# pcb_rfic_nrf905_final.net
KiCad netlist of a schematic drawn in EAGLE
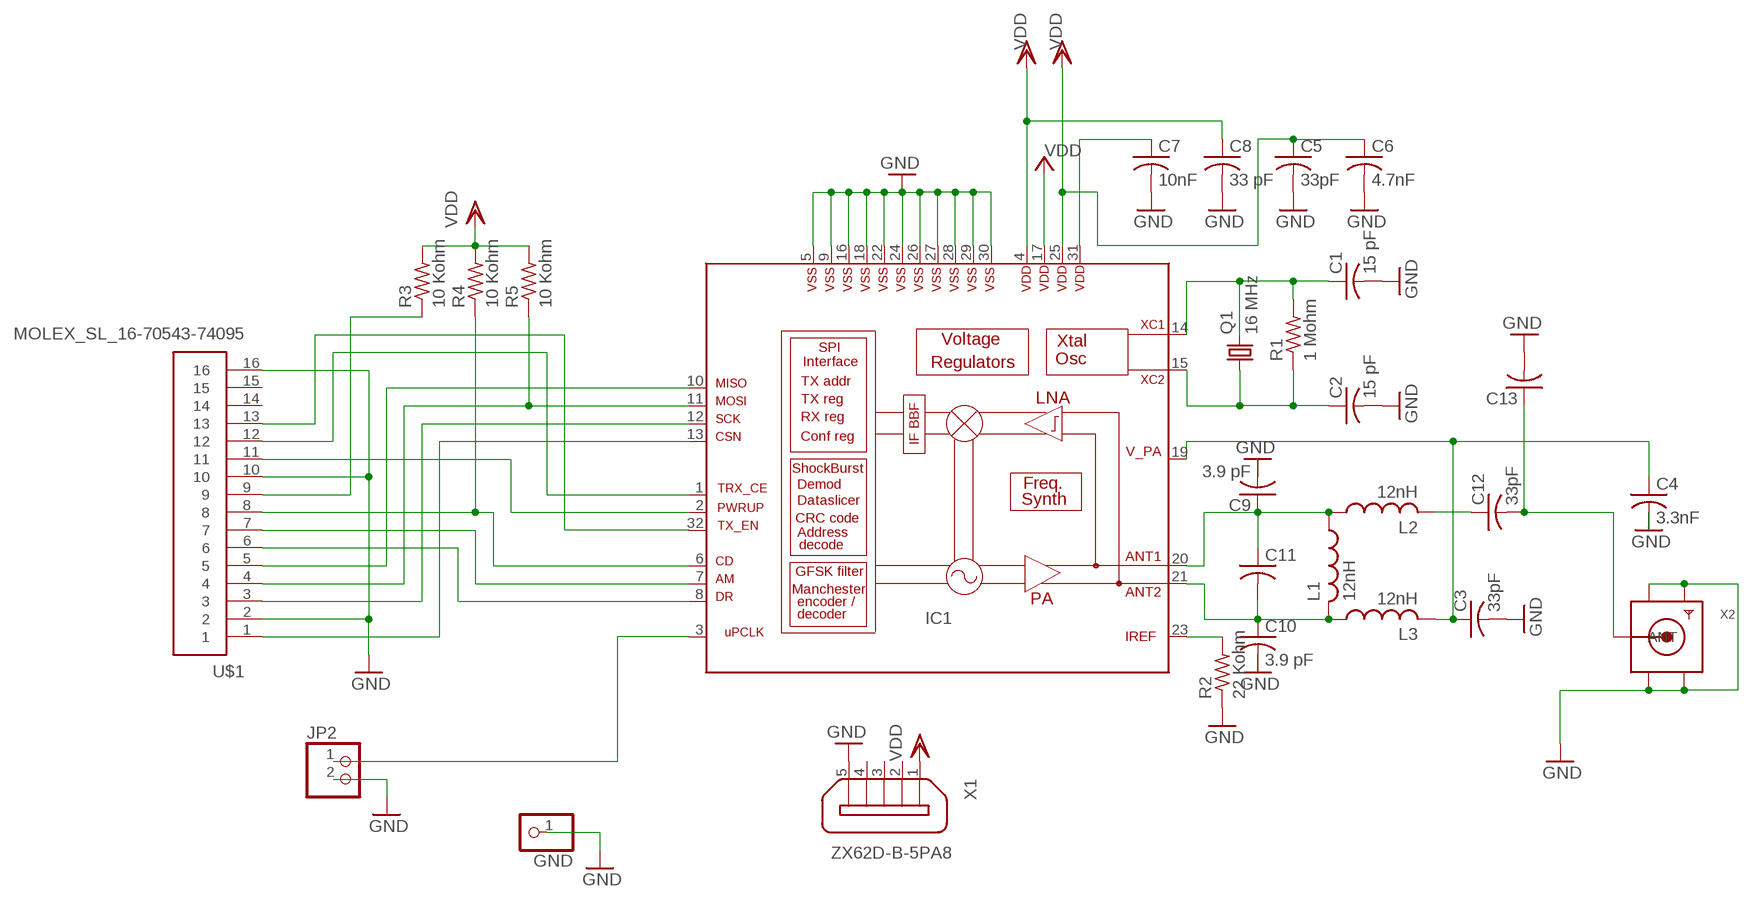
[diagram p0: schematic, sheet 1]

(export (version "E")
  (design (tool "Eeschema 10.0.6"))
  (components
    (comp (ref "C1")
      (value "15 pF")
      (footprint "eagle-import:C0603")
      (fields (field (name "MF") "MULTICOMP PRO") (field (name "MPN") "MCMT18N150F500CT"))
      (libsource (lib "eagle-import") (part "C-USC0603"))
    )
    (comp (ref "C2")
      (value "15 pF")
      (footprint "eagle-import:C0603")
      (fields (field (name "MF") "MULTICOMP PRO") (field (name "MPN") "MCMT18N150F500CT"))
      (libsource (lib "eagle-import") (part "C-USC0603"))
    )
    (comp (ref "C3")
      (value "33pF")
      (footprint "eagle-import:C0603")
      (fields (field (name "MF") "MULTICOMP PRO") (field (name "MPN") "MCMT18N330F100CT"))
      (libsource (lib "eagle-import") (part "C-USC0603"))
    )
    (comp (ref "C4")
      (value "3.3nF")
      (footprint "eagle-import:C0603")
      (fields (field (name "MF") "KEMET") (field (name "MPN") "C0603C332J5JACTU"))
      (libsource (lib "eagle-import") (part "C-USC0603"))
    )
    (comp (ref "C5")
      (value "33pF")
      (footprint "eagle-import:C0603")
      (fields (field (name "MF") "MULTICOMP PRO") (field (name "MPN") "MCMT18N330F100CT"))
      (libsource (lib "eagle-import") (part "C-USC0603"))
    )
    (comp (ref "C6")
      (value "4.7nF")
      (footprint "eagle-import:C0603")
      (fields (field (name "MF") "KEMET") (field (name "MPN") "C0603X472K5RAC3316"))
      (libsource (lib "eagle-import") (part "C-USC0603"))
    )
    (comp (ref "C7")
      (value "10nF")
      (footprint "eagle-import:C0603")
      (fields (field (name "MF") "TDK") (field (name "MPN") "CGA3E2C0G1H103J080AA"))
      (libsource (lib "eagle-import") (part "C-USC0603"))
    )
    (comp (ref "C8")
      (value "33 pF")
      (footprint "eagle-import:C0603")
      (fields (field (name "MF") "KEMET") (field (name "MPN") "C0603C330J5GACTU"))
      (libsource (lib "eagle-import") (part "C-USC0603"))
    )
    (comp (ref "C9")
      (value "3.9 pF")
      (footprint "eagle-import:C0603")
      (fields (field (name "MF") "AVX") (field (name "MPN") "06035A3R9DAT2A"))
      (libsource (lib "eagle-import") (part "C-USC0603"))
    )
    (comp (ref "C10")
      (value "3.9 pF")
      (footprint "eagle-import:C0603")
      (fields (field (name "MF") "AVX") (field (name "MPN") "06035A3R9DAT2A"))
      (libsource (lib "eagle-import") (part "C-USC0603"))
    )
    (comp (ref "C11")
      (value "C-USC0603")
      (footprint "eagle-import:C0603")
      (libsource (lib "eagle-import") (part "C-USC0603"))
    )
    (comp (ref "C12")
      (value "33pF")
      (footprint "eagle-import:C0603")
      (fields (field (name "MF") "MULTICOMP PRO") (field (name "MPN") "MCMT18N330F100CT"))
      (libsource (lib "eagle-import") (part "C-USC0603"))
    )
    (comp (ref "C13")
      (value "C-USC0603")
      (footprint "eagle-import:C0603")
      (libsource (lib "eagle-import") (part "C-USC0603"))
    )
    (comp (ref "GND")
      (value "PINHD-1X1")
      (footprint "eagle-import:1X01")
      (fields (field (name "MF") "VISHAY") (field (name "MPN") "VO615A-1X019T"))
      (libsource (lib "eagle-import") (part "PINHD-1X1"))
    )
    (comp (ref "IC1")
      (value "NRF905")
      (footprint "eagle-import:LQFP-32")
      (libsource (lib "eagle-import") (part "NRF905"))
    )
    (comp (ref "JP2")
      (value "PINHD-1X2")
      (footprint "eagle-import:1X02")
      (libsource (lib "eagle-import") (part "PINHD-1X2"))
    )
    (comp (ref "L1")
      (value "12nH")
      (footprint "eagle-import:0204V")
      (fields (field (name "MF") "MULTICOMP PRO") (field (name "MPN") "MCFT000084"))
      (libsource (lib "eagle-import") (part "L-US0204V"))
    )
    (comp (ref "L2")
      (value "12nH")
      (footprint "eagle-import:0204V")
      (fields (field (name "MF") "MULTICOMP PRO") (field (name "MPN") "MCFT000084"))
      (libsource (lib "eagle-import") (part "L-US0204V"))
    )
    (comp (ref "L3")
      (value "12nH")
      (footprint "eagle-import:0204V")
      (fields (field (name "MF") "MULTICOMP PRO") (field (name "MPN") "MCFT000084"))
      (libsource (lib "eagle-import") (part "L-US0204V"))
    )
    (comp (ref "Q1")
      (value "16 MHz")
      (footprint "eagle-import:HC18U-V")
      (libsource (lib "eagle-import") (part "CRYSTALHC18U-V"))
    )
    (comp (ref "R1")
      (value "1 Mohm")
      (footprint "eagle-import:R0603")
      (fields (field (name "MF") "MULTICOMP PRO") (field (name "MPN") "MCWR06X1004FTL"))
      (libsource (lib "eagle-import") (part "rcl_2_R-US_R0603"))
    )
    (comp (ref "R2")
      (value "22 Kohm")
      (footprint "eagle-import:R0603")
      (libsource (lib "eagle-import") (part "rcl_2_R-US_R0603"))
    )
    (comp (ref "R3")
      (value "10 Kohm")
      (footprint "eagle-import:R0603")
      (libsource (lib "eagle-import") (part "rcl_2_R-US_R0603"))
    )
    (comp (ref "R4")
      (value "10 Kohm")
      (footprint "eagle-import:R0603")
      (libsource (lib "eagle-import") (part "R-US_R0603"))
    )
    (comp (ref "R5")
      (value "10 Kohm")
      (footprint "eagle-import:R0603")
      (libsource (lib "eagle-import") (part "R-US_R0603"))
    )
    (comp (ref "U$1")
      (value "MOLEX_SL_16-70543-74095")
      (footprint "eagle-import:SL_70543_16")
      (libsource (lib "eagle-import") (part "MOLEX_SL_16-70543-74095"))
    )
    (comp (ref "X1")
      (value "ZX62D-B-5PA8")
      (footprint "eagle-import:ZX62D-B-5PA8")
      (fields (field (name "MF") "Hirose") (field (name "OC_NEWARK") "unknown"))
      (libsource (lib "eagle-import") (part "ZX62D-B-5PA8"))
    )
    (comp (ref "X2")
      (value "SMACONNECTOR_EDGE")
      (footprint "eagle-import:SMA_EDGELAUNCH")
      (libsource (lib "eagle-import") (part "SMACONNECTOR_EDGE"))
    )
  )
  (nets
    (net (code "1") (name "GND") (class "Default")
      (node (ref "C1") (pin "2") (pinfunction "2_2") (pintype "passive"))
      (node (ref "C10") (pin "2") (pinfunction "2_2") (pintype "passive"))
      (node (ref "C13") (pin "2") (pinfunction "2_2") (pintype "passive"))
      (node (ref "C2") (pin "2") (pinfunction "2_2") (pintype "passive"))
      (node (ref "C3") (pin "2") (pinfunction "2_2") (pintype "passive"))
      (node (ref "C4") (pin "2") (pinfunction "2_2") (pintype "passive"))
      (node (ref "C5") (pin "2") (pinfunction "2_2") (pintype "passive"))
      (node (ref "C6") (pin "2") (pinfunction "2_2") (pintype "passive"))
      (node (ref "C7") (pin "2") (pinfunction "2_2") (pintype "passive"))
      (node (ref "C8") (pin "2") (pinfunction "2_2") (pintype "passive"))
      (node (ref "C9") (pin "2") (pinfunction "2_2") (pintype "passive"))
      (node (ref "GND") (pin "1") (pinfunction "1_1") (pintype "passive"))
      (node (ref "IC1") (pin "16") (pinfunction "VSS16_16") (pintype "passive"))
      (node (ref "IC1") (pin "18") (pinfunction "VSS18_18") (pintype "passive"))
      (node (ref "IC1") (pin "22") (pinfunction "VSS22_22") (pintype "passive"))
      (node (ref "IC1") (pin "24") (pinfunction "VSS24_24") (pintype "passive"))
      (node (ref "IC1") (pin "26") (pinfunction "VSS26_26") (pintype "passive"))
      (node (ref "IC1") (pin "27") (pinfunction "VSS27_27") (pintype "passive"))
      (node (ref "IC1") (pin "28") (pinfunction "VSS28_28") (pintype "passive"))
      (node (ref "IC1") (pin "29") (pinfunction "VSS29_29") (pintype "passive"))
      (node (ref "IC1") (pin "30") (pinfunction "VSS30_30") (pintype "passive"))
      (node (ref "IC1") (pin "5") (pinfunction "VSS5_5") (pintype "passive"))
      (node (ref "IC1") (pin "9") (pinfunction "VSS9_9") (pintype "passive"))
      (node (ref "JP2") (pin "2") (pinfunction "2_2") (pintype "passive"))
      (node (ref "R2") (pin "1") (pinfunction "1_1") (pintype "passive"))
      (node (ref "U$1") (pin "10") (pinfunction "10_10") (pintype "bidirectional"))
      (node (ref "U$1") (pin "16") (pinfunction "16_16") (pintype "bidirectional"))
      (node (ref "U$1") (pin "2") (pinfunction "2_2") (pintype "bidirectional"))
      (node (ref "X1") (pin "5") (pinfunction "5_5") (pintype "passive"))
      (node (ref "X2") (pin "GND@1") (pinfunction "GND4_GND@1") (pintype "power_in"))
      (node (ref "X2") (pin "GND@2") (pinfunction "GND3_GND@2") (pintype "power_in"))
      (node (ref "X2") (pin "GND@3") (pinfunction "GND2_GND@3") (pintype "power_in"))
      (node (ref "X2") (pin "GND@4") (pinfunction "GND1_GND@4") (pintype "power_in"))
    )
    (net (code "2") (name "Net-(C12-Pad1)") (class "Default")
      (node (ref "C12") (pin "1") (pinfunction "1_1") (pintype "passive"))
      (node (ref "L2") (pin "2") (pinfunction "2_2") (pintype "passive"))
    )
    (net (code "3") (name "Net-(IC1-AM)") (class "Default")
      (node (ref "IC1") (pin "7") (pinfunction "AM_7") (pintype "passive"))
      (node (ref "U$1") (pin "7") (pinfunction "7_7") (pintype "bidirectional"))
    )
    (net (code "4") (name "Net-(IC1-ANT1)") (class "Default")
      (node (ref "C11") (pin "1") (pinfunction "1_1") (pintype "passive"))
      (node (ref "C9") (pin "1") (pinfunction "1_1") (pintype "passive"))
      (node (ref "IC1") (pin "20") (pinfunction "ANT1_20") (pintype "passive"))
      (node (ref "L1") (pin "1") (pinfunction "1_1") (pintype "passive"))
      (node (ref "L2") (pin "1") (pinfunction "1_1") (pintype "passive"))
    )
    (net (code "5") (name "Net-(IC1-ANT2)") (class "Default")
      (node (ref "C10") (pin "1") (pinfunction "1_1") (pintype "passive"))
      (node (ref "C11") (pin "2") (pinfunction "2_2") (pintype "passive"))
      (node (ref "IC1") (pin "21") (pinfunction "ANT2_21") (pintype "passive"))
      (node (ref "L1") (pin "2") (pinfunction "2_2") (pintype "passive"))
      (node (ref "L3") (pin "1") (pinfunction "1_1") (pintype "passive"))
    )
    (net (code "6") (name "Net-(IC1-CD)") (class "Default")
      (node (ref "IC1") (pin "6") (pinfunction "CD_6") (pintype "passive"))
      (node (ref "R4") (pin "1") (pinfunction "1_1") (pintype "passive"))
      (node (ref "U$1") (pin "8") (pinfunction "8_8") (pintype "bidirectional"))
    )
    (net (code "7") (name "Net-(IC1-CSN)") (class "Default")
      (node (ref "IC1") (pin "13") (pinfunction "CSN_13") (pintype "passive"))
      (node (ref "U$1") (pin "1") (pinfunction "1_1") (pintype "bidirectional"))
    )
    (net (code "8") (name "Net-(IC1-DR)") (class "Default")
      (node (ref "IC1") (pin "8") (pinfunction "DR_8") (pintype "passive"))
      (node (ref "U$1") (pin "6") (pinfunction "6_6") (pintype "bidirectional"))
    )
    (net (code "9") (name "Net-(IC1-DVDD1V2)") (class "Default")
      (node (ref "C7") (pin "1") (pinfunction "1_1") (pintype "passive"))
      (node (ref "IC1") (pin "31") (pinfunction "DVDD1V2_31") (pintype "passive"))
    )
    (net (code "10") (name "Net-(IC1-IREF)") (class "Default")
      (node (ref "IC1") (pin "23") (pinfunction "IREF_23") (pintype "passive"))
      (node (ref "R2") (pin "2") (pinfunction "2_2") (pintype "passive"))
    )
    (net (code "11") (name "Net-(IC1-MISO)") (class "Default")
      (node (ref "IC1") (pin "10") (pinfunction "MISO_10") (pintype "passive"))
      (node (ref "U$1") (pin "5") (pinfunction "5_5") (pintype "bidirectional"))
    )
    (net (code "12") (name "Net-(IC1-MOSI)") (class "Default")
      (node (ref "IC1") (pin "11") (pinfunction "MOSI_11") (pintype "passive"))
      (node (ref "R5") (pin "1") (pinfunction "1_1") (pintype "passive"))
      (node (ref "U$1") (pin "4") (pinfunction "4_4") (pintype "bidirectional"))
    )
    (net (code "13") (name "Net-(IC1-PWR_UP)") (class "Default")
      (node (ref "IC1") (pin "2") (pinfunction "PWR_UP_2") (pintype "passive"))
      (node (ref "U$1") (pin "11") (pinfunction "11_11") (pintype "bidirectional"))
    )
    (net (code "14") (name "Net-(IC1-SCK)") (class "Default")
      (node (ref "IC1") (pin "12") (pinfunction "SCK_12") (pintype "passive"))
      (node (ref "U$1") (pin "3") (pinfunction "3_3") (pintype "bidirectional"))
    )
    (net (code "15") (name "Net-(IC1-TRX_CE)") (class "Default")
      (node (ref "IC1") (pin "1") (pinfunction "TRX_CE_1") (pintype "passive"))
      (node (ref "U$1") (pin "12") (pinfunction "12_12") (pintype "bidirectional"))
    )
    (net (code "16") (name "Net-(IC1-TX_EN)") (class "Default")
      (node (ref "IC1") (pin "32") (pinfunction "TX_EN_32") (pintype "passive"))
      (node (ref "U$1") (pin "13") (pinfunction "13_13") (pintype "bidirectional"))
    )
    (net (code "17") (name "Net-(IC1-UPCLK)") (class "Default")
      (node (ref "IC1") (pin "3") (pinfunction "UPCLK_3") (pintype "passive"))
      (node (ref "JP2") (pin "1") (pinfunction "1_1") (pintype "passive"))
    )
    (net (code "18") (name "Net-(IC1-VDD_PA)") (class "Default")
      (node (ref "C3") (pin "1") (pinfunction "1_1") (pintype "passive"))
      (node (ref "C4") (pin "1") (pinfunction "1_1") (pintype "passive"))
      (node (ref "IC1") (pin "19") (pinfunction "VDD_PA_19") (pintype "power_in"))
      (node (ref "L3") (pin "2") (pinfunction "2_2") (pintype "passive"))
    )
    (net (code "19") (name "Net-(IC1-XC1)") (class "Default")
      (node (ref "C1") (pin "1") (pinfunction "1_1") (pintype "passive"))
      (node (ref "IC1") (pin "14") (pinfunction "XC1_14") (pintype "passive"))
      (node (ref "Q1") (pin "2") (pinfunction "2_2") (pintype "passive"))
      (node (ref "R1") (pin "2") (pinfunction "2_2") (pintype "passive"))
    )
    (net (code "20") (name "Net-(IC1-XC2)") (class "Default")
      (node (ref "C2") (pin "1") (pinfunction "1_1") (pintype "passive"))
      (node (ref "IC1") (pin "15") (pinfunction "XC2_15") (pintype "passive"))
      (node (ref "Q1") (pin "1") (pinfunction "1_1") (pintype "passive"))
      (node (ref "R1") (pin "1") (pinfunction "1_1") (pintype "passive"))
    )
    (net (code "21") (name "Net-(R3-Pad1)") (class "Default")
      (node (ref "R3") (pin "1") (pinfunction "1_1") (pintype "passive"))
      (node (ref "U$1") (pin "9") (pinfunction "9_9") (pintype "bidirectional"))
    )
    (net (code "22") (name "Net-(X2-ANT)") (class "Default")
      (node (ref "C12") (pin "2") (pinfunction "2_2") (pintype "passive"))
      (node (ref "C13") (pin "1") (pinfunction "1_1") (pintype "passive"))
      (node (ref "X2") (pin "P") (pinfunction "ANT_P") (pintype "bidirectional"))
    )
    (net (code "23") (name "VCC") (class "Default")
      (node (ref "IC1") (pin "17") (pinfunction "VDD17_17") (pintype "power_in"))
    )
    (net (code "24") (name "VDD") (class "Default")
      (node (ref "C5") (pin "1") (pinfunction "1_1") (pintype "passive"))
      (node (ref "C6") (pin "1") (pinfunction "1_1") (pintype "passive"))
      (node (ref "C8") (pin "1") (pinfunction "1_1") (pintype "passive"))
      (node (ref "IC1") (pin "25") (pinfunction "VDD25_25") (pintype "power_in"))
      (node (ref "IC1") (pin "4") (pinfunction "VDD4_4") (pintype "power_in"))
      (node (ref "R3") (pin "2") (pinfunction "2_2") (pintype "passive"))
      (node (ref "R4") (pin "2") (pinfunction "2_2") (pintype "passive"))
      (node (ref "R5") (pin "2") (pinfunction "2_2") (pintype "passive"))
      (node (ref "X1") (pin "1") (pinfunction "1_1") (pintype "passive"))
    )
    (net (code "25") (name "unconnected-(U$1-Pad14)") (class "Default")
      (node (ref "U$1") (pin "14") (pinfunction "14_14") (pintype "bidirectional"))
    )
    (net (code "26") (name "unconnected-(U$1-Pad15)") (class "Default")
      (node (ref "U$1") (pin "15") (pinfunction "15_15") (pintype "bidirectional"))
    )
    (net (code "27") (name "unconnected-(X1-Pad2)") (class "Default")
      (node (ref "X1") (pin "2") (pinfunction "2_2") (pintype "passive"))
    )
    (net (code "28") (name "unconnected-(X1-Pad3)") (class "Default")
      (node (ref "X1") (pin "3") (pinfunction "3_3") (pintype "passive"))
    )
    (net (code "29") (name "unconnected-(X1-Pad4)") (class "Default")
      (node (ref "X1") (pin "4") (pinfunction "4_4") (pintype "passive"))
    )
  )
)
